# Arduino_MEGA_2560-Rev3.net
KiCad netlist of a schematic drawn in EAGLE
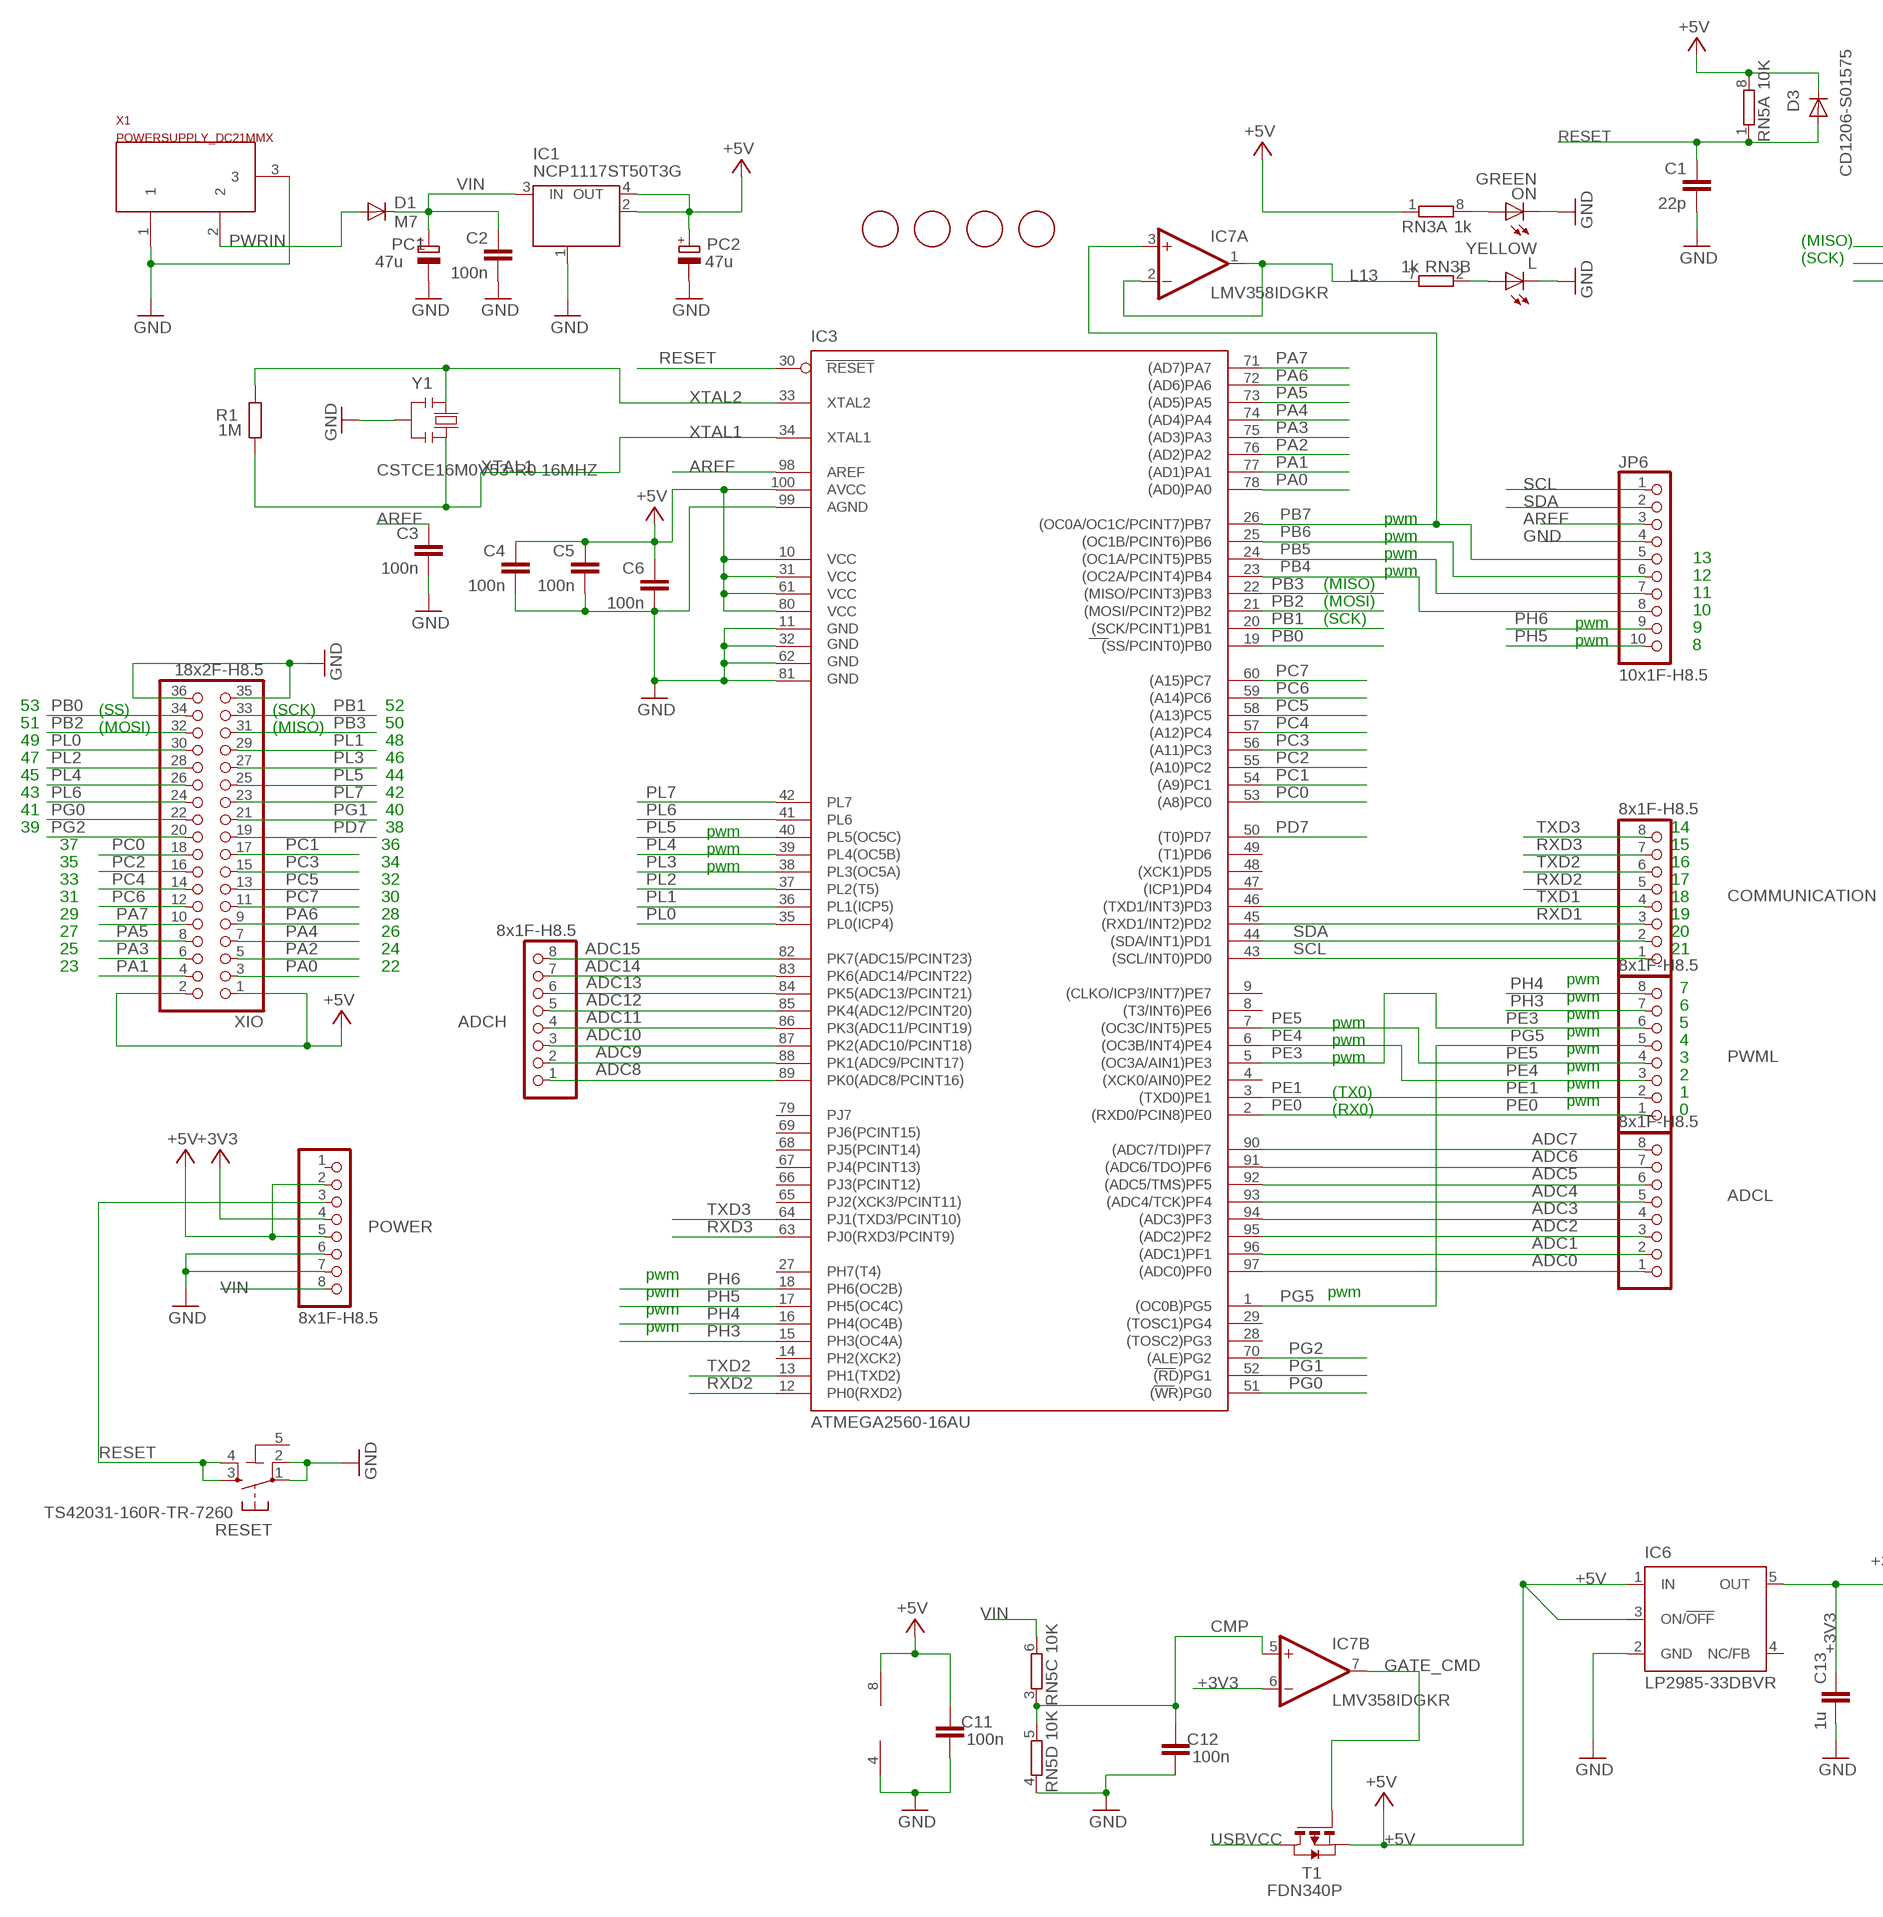
[diagram p0: schematic, sheet 1, part 1 of 2]
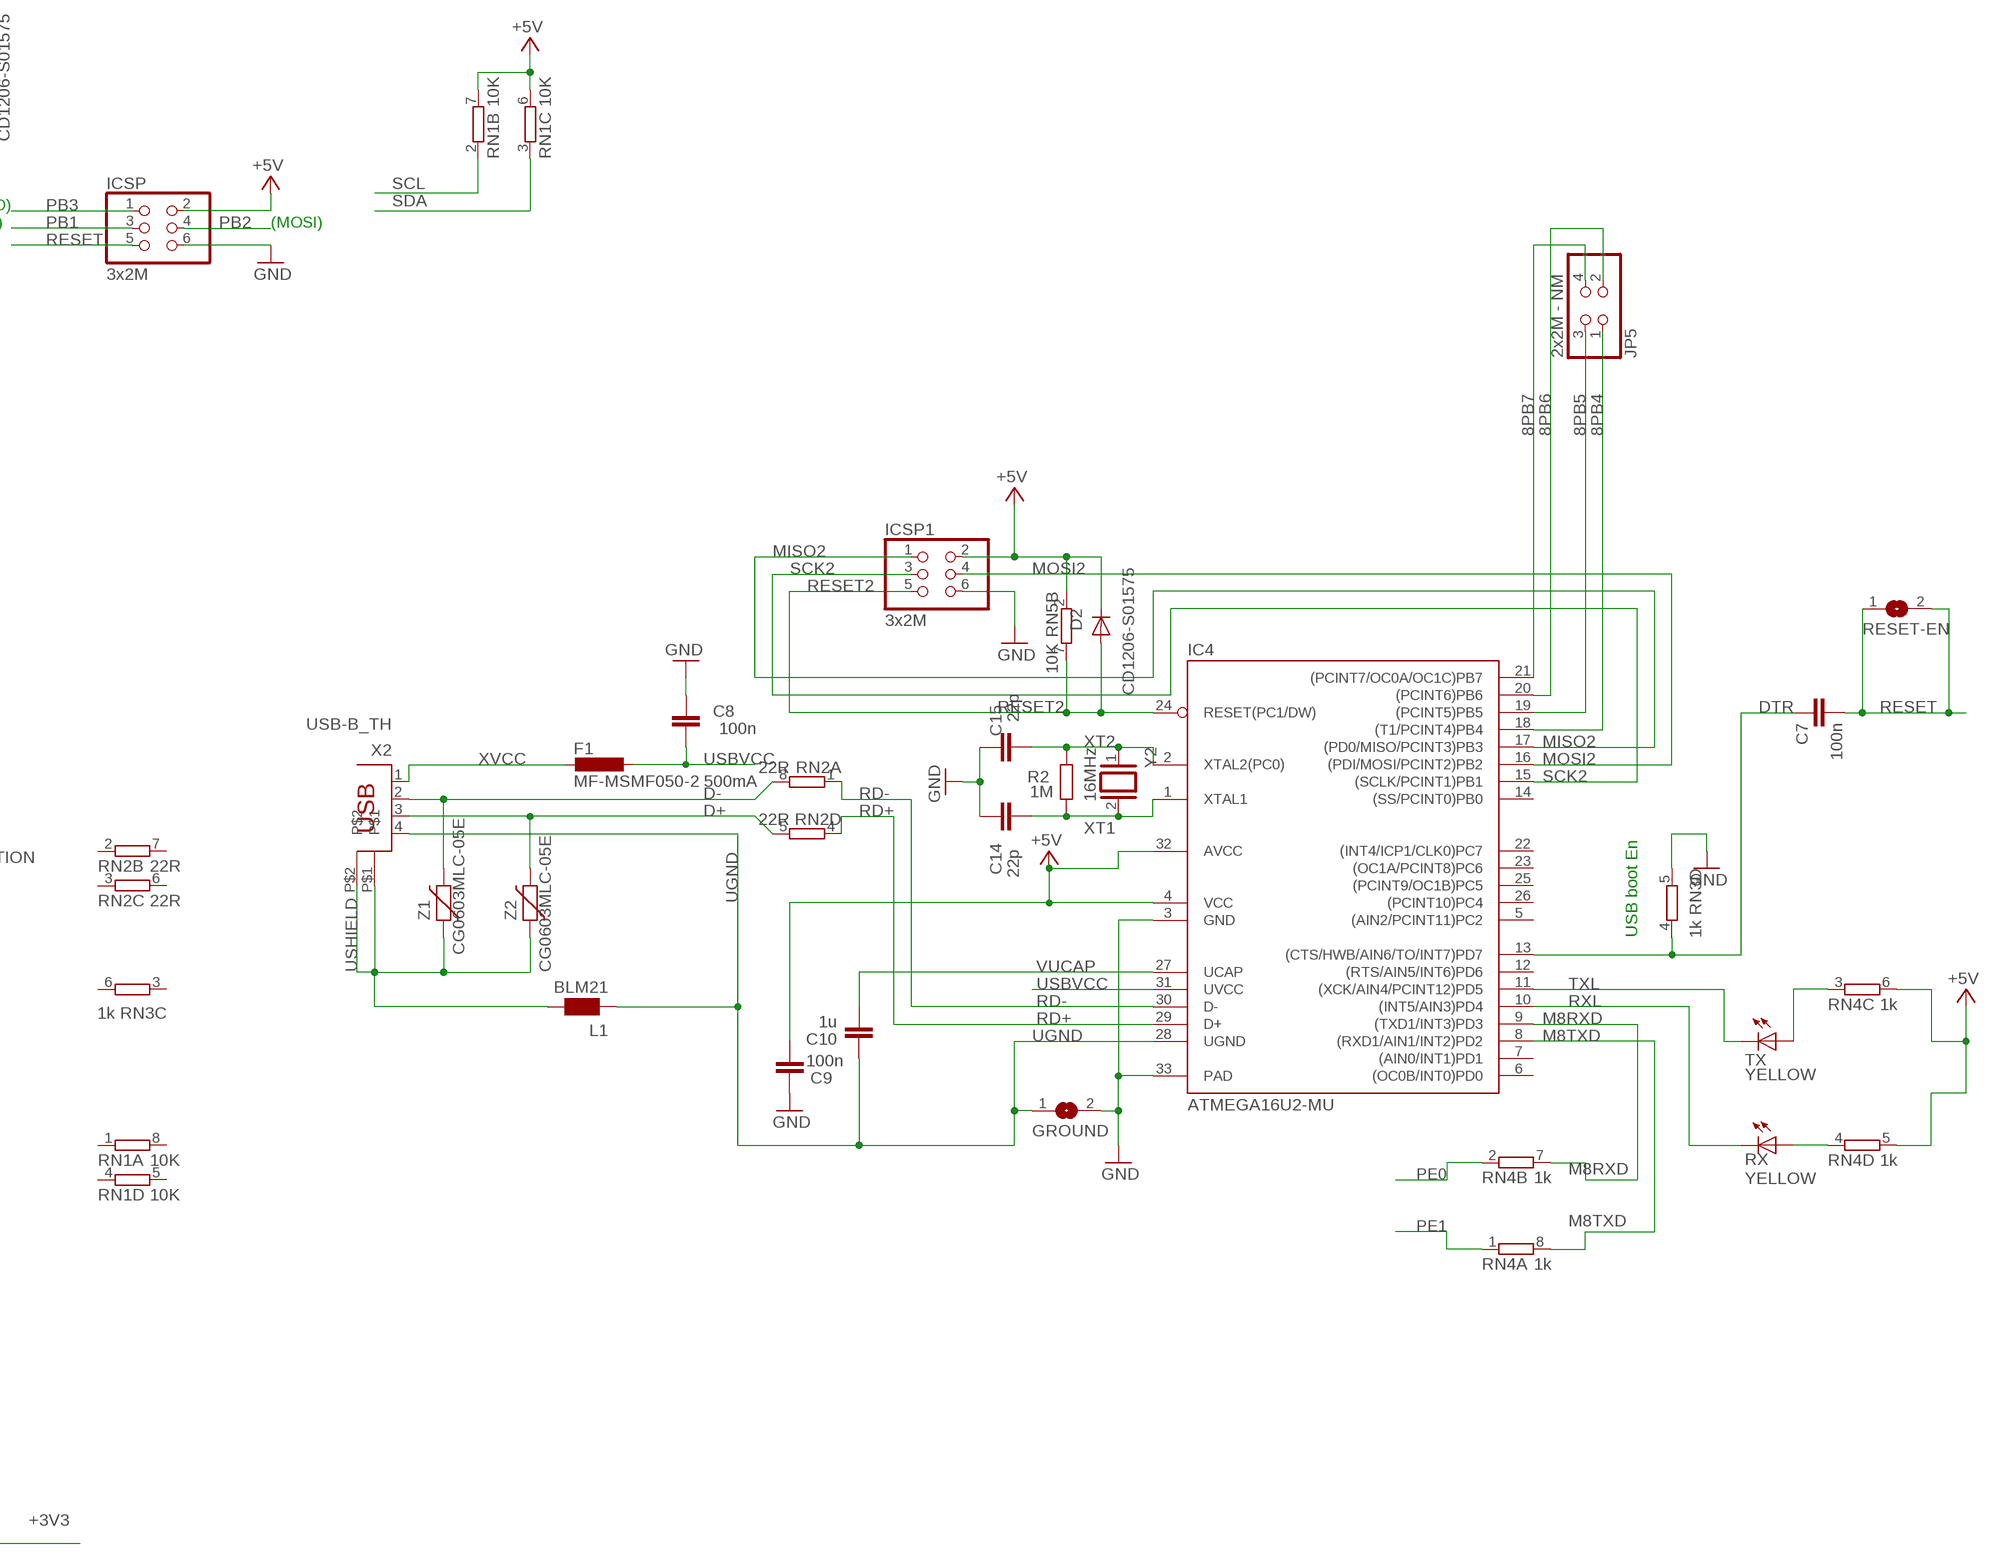
[diagram p1: schematic, sheet 1, part 2 of 2]

(export (version "E")
  (design (tool "Eeschema 10.0.6"))
  (components
    (comp (ref "ADCH")
      (value "8x1F-H8.5")
      (footprint "eagle-import:1X08")
      (libsource (lib "eagle-import") (part "PINHD-1X8"))
    )
    (comp (ref "ADCL")
      (value "8x1F-H8.5")
      (footprint "eagle-import:1X08")
      (libsource (lib "eagle-import") (part "PINHD-1X8"))
    )
    (comp (ref "C1")
      (value "22p")
      (footprint "eagle-import:C0603-ROUND")
      (libsource (lib "eagle-import") (part "C-EU0603-RND"))
    )
    (comp (ref "C2")
      (value "100n")
      (footprint "eagle-import:C0603-ROUND")
      (libsource (lib "eagle-import") (part "C-EU0603-RND"))
    )
    (comp (ref "C3")
      (value "100n")
      (footprint "eagle-import:C0603-ROUND")
      (libsource (lib "eagle-import") (part "C-EU0603-RND"))
    )
    (comp (ref "C4")
      (value "100n")
      (footprint "eagle-import:C0603-ROUND")
      (libsource (lib "eagle-import") (part "C-EU0603-RND"))
    )
    (comp (ref "C5")
      (value "100n")
      (footprint "eagle-import:C0603-ROUND")
      (libsource (lib "eagle-import") (part "C-EU0603-RND"))
    )
    (comp (ref "C6")
      (value "100n")
      (footprint "eagle-import:C0603-ROUND")
      (libsource (lib "eagle-import") (part "C-EU0603-RND"))
    )
    (comp (ref "C7")
      (value "100n")
      (footprint "eagle-import:C0603-ROUND")
      (libsource (lib "eagle-import") (part "C-EU0603-RND"))
    )
    (comp (ref "C8")
      (value "100n")
      (footprint "eagle-import:C0603-ROUND")
      (libsource (lib "eagle-import") (part "C-EU0603-RND"))
    )
    (comp (ref "C9")
      (value "100n")
      (footprint "eagle-import:C0603-ROUND")
      (libsource (lib "eagle-import") (part "C-EU0603-RND"))
    )
    (comp (ref "C10")
      (value "1u")
      (footprint "eagle-import:C0603-ROUND")
      (libsource (lib "eagle-import") (part "C-EU0603-RND"))
    )
    (comp (ref "C11")
      (value "100n")
      (footprint "eagle-import:C0603-ROUND")
      (libsource (lib "eagle-import") (part "C-EU0603-RND"))
    )
    (comp (ref "C12")
      (value "100n")
      (footprint "eagle-import:C0603-ROUND")
      (libsource (lib "eagle-import") (part "C-EU0603-RND"))
    )
    (comp (ref "C13")
      (value "1u")
      (footprint "eagle-import:C0603-ROUND")
      (libsource (lib "eagle-import") (part "C-EU0603-RND"))
    )
    (comp (ref "C14")
      (value "22p")
      (footprint "eagle-import:C0603-ROUND")
      (libsource (lib "eagle-import") (part "C-EU0603-RND"))
    )
    (comp (ref "C15")
      (value "22p")
      (footprint "eagle-import:C0603-ROUND")
      (libsource (lib "eagle-import") (part "C-EU0603-RND"))
    )
    (comp (ref "COMMUNICATION")
      (value "8x1F-H8.5")
      (footprint "eagle-import:1X08")
      (libsource (lib "eagle-import") (part "PINHD-1X8"))
    )
    (comp (ref "D1")
      (value "M7")
      (footprint "eagle-import:SMB")
      (libsource (lib "eagle-import") (part "DIODE-SMB"))
    )
    (comp (ref "D2")
      (value "CD1206-S01575")
      (footprint "eagle-import:MINIMELF")
      (libsource (lib "eagle-import") (part "DIODE-MINIMELF"))
    )
    (comp (ref "D3")
      (value "CD1206-S01575")
      (footprint "eagle-import:MINIMELF")
      (libsource (lib "eagle-import") (part "DIODE-MINIMELF"))
    )
    (comp (ref "F1")
      (value "MF-MSMF050-2 500mA")
      (footprint "eagle-import:L1812")
      (libsource (lib "eagle-import") (part "L-EUL1812"))
    )
    (comp (ref "FD1")
      (value "FIDUCIALMOUNT")
      (footprint "eagle-import:FIDUCIA-MOUNT")
      (libsource (lib "eagle-import") (part "FIDUCIALMOUNT"))
    )
    (comp (ref "FD2")
      (value "FIDUCIALMOUNT")
      (footprint "eagle-import:FIDUCIA-MOUNT")
      (libsource (lib "eagle-import") (part "FIDUCIALMOUNT"))
    )
    (comp (ref "FD3")
      (value "FIDUCIALMOUNT")
      (footprint "eagle-import:FIDUCIA-MOUNT")
      (libsource (lib "eagle-import") (part "FIDUCIALMOUNT"))
    )
    (comp (ref "FD4")
      (value "FIDUCIALMOUNT")
      (footprint "eagle-import:FIDUCIA-MOUNT")
      (libsource (lib "eagle-import") (part "FIDUCIALMOUNT"))
    )
    (comp (ref "GROUND")
      (value "SJ")
      (footprint "eagle-import:SJ")
      (libsource (lib "eagle-import") (part "SJ"))
    )
    (comp (ref "IC1")
      (value "NCP1117ST50T3G")
      (footprint "eagle-import:SOT223")
      (libsource (lib "eagle-import") (part "MC33269ST-3.3T3"))
    )
    (comp (ref "IC3")
      (value "ATMEGA2560-16AU")
      (footprint "eagle-import:TQFP100")
      (libsource (lib "eagle-import") (part "ATMEGA2560AU2560-16"))
    )
    (comp (ref "IC4")
      (value "ATMEGA16U2-MU")
      (footprint "eagle-import:MLF32")
      (libsource (lib "eagle-import") (part "ATMEGA16U2-MU"))
    )
    (comp (ref "IC6")
      (value "LP2985-33DBVR")
      (footprint "eagle-import:SOT23-DBV")
      (libsource (lib "eagle-import") (part "LP2985-XXDBVR33"))
    )
    (comp (ref "IC7")
      (value "LMV358IDGKR")
      (footprint "eagle-import:MSOP08")
      (libsource (lib "eagle-import") (part "LMV358?MMX"))
    )
    (comp (ref "ICSP")
      (value "3x2M")
      (footprint "eagle-import:2X03")
      (libsource (lib "eagle-import") (part "PINHD-2X3"))
    )
    (comp (ref "ICSP1")
      (value "3x2M")
      (footprint "eagle-import:2X03")
      (libsource (lib "eagle-import") (part "PINHD-2X3"))
    )
    (comp (ref "JP5")
      (value "2x2M - NM")
      (footprint "eagle-import:2X02")
      (libsource (lib "eagle-import") (part "PINHD-2X2"))
    )
    (comp (ref "JP6")
      (value "10x1F-H8.5")
      (footprint "eagle-import:1X10")
      (libsource (lib "eagle-import") (part "PINHD-1X10_ARD"))
    )
    (comp (ref "L")
      (value "YELLOW")
      (footprint "eagle-import:CHIP-LED0805")
      (libsource (lib "eagle-import") (part "LEDCHIP-LED0805"))
    )
    (comp (ref "L1")
      (value "BLM21")
      (footprint "eagle-import:0805")
      (libsource (lib "eagle-import") (part "WE-CBF_0805"))
    )
    (comp (ref "ON")
      (value "GREEN")
      (footprint "eagle-import:CHIP-LED0805")
      (libsource (lib "eagle-import") (part "LEDCHIP-LED0805"))
    )
    (comp (ref "PC1")
      (value "47u")
      (footprint "eagle-import:PANASONIC_D")
      (libsource (lib "eagle-import") (part "CPOL-EUD"))
    )
    (comp (ref "PC2")
      (value "47u")
      (footprint "eagle-import:PANASONIC_D")
      (libsource (lib "eagle-import") (part "CPOL-EUD"))
    )
    (comp (ref "POWER")
      (value "8x1F-H8.5")
      (footprint "eagle-import:1X08")
      (libsource (lib "eagle-import") (part "PINHD-1X8"))
    )
    (comp (ref "PWML")
      (value "8x1F-H8.5")
      (footprint "eagle-import:1X08")
      (libsource (lib "eagle-import") (part "PINHD-1X8"))
    )
    (comp (ref "R1")
      (value "1M")
      (footprint "eagle-import:R0603-ROUND")
      (libsource (lib "eagle-import") (part "R-EU_R0603"))
    )
    (comp (ref "R2")
      (value "1M")
      (footprint "eagle-import:R0603-ROUND")
      (libsource (lib "eagle-import") (part "R-EU_R0603"))
    )
    (comp (ref "RESET")
      (value "TS42031-160R-TR-7260")
      (footprint "eagle-import:TS42")
      (libsource (lib "eagle-import") (part "TS42"))
    )
    (comp (ref "RESET-EN")
      (value "SJ")
      (footprint "eagle-import:SJ")
      (libsource (lib "eagle-import") (part "SJ"))
    )
    (comp (ref "RN1")
      (value "10K")
      (footprint "eagle-import:CAT16")
      (libsource (lib "eagle-import") (part "4R-NCAT16"))
    )
    (comp (ref "RN2")
      (value "22R")
      (footprint "eagle-import:CAY16")
      (libsource (lib "eagle-import") (part "4R-NCAY16"))
    )
    (comp (ref "RN3")
      (value "1k")
      (footprint "eagle-import:CAY16")
      (libsource (lib "eagle-import") (part "4R-NCAY16"))
    )
    (comp (ref "RN4")
      (value "1k")
      (footprint "eagle-import:CAY16")
      (libsource (lib "eagle-import") (part "4R-NCAY16"))
    )
    (comp (ref "RN5")
      (value "10K")
      (footprint "eagle-import:CAT16")
      (libsource (lib "eagle-import") (part "4R-NCAT16"))
    )
    (comp (ref "RX")
      (value "YELLOW")
      (footprint "eagle-import:CHIP-LED0805")
      (libsource (lib "eagle-import") (part "LEDCHIP-LED0805"))
    )
    (comp (ref "T1")
      (value "FDN340P")
      (footprint "eagle-import:SOT-23")
      (libsource (lib "eagle-import") (part "PMOSSOT23"))
    )
    (comp (ref "TX")
      (value "YELLOW")
      (footprint "eagle-import:CHIP-LED0805")
      (libsource (lib "eagle-import") (part "LEDCHIP-LED0805"))
    )
    (comp (ref "X1")
      (value "POWERSUPPLY_DC21MMX")
      (footprint "eagle-import:POWERSUPPLY_DC-21MM")
      (libsource (lib "eagle-import") (part "POWERSUPPLY_DC21MMX"))
    )
    (comp (ref "X2")
      (value "USB-B_TH")
      (footprint "eagle-import:PN61729")
      (libsource (lib "eagle-import") (part "PN61729"))
    )
    (comp (ref "XIO")
      (value "18x2F-H8.5")
      (footprint "eagle-import:2X18")
      (libsource (lib "eagle-import") (part "PINHD-2X18"))
    )
    (comp (ref "Y1")
      (value "CSTCE16M0V53-R0 16MHZ")
      (footprint "eagle-import:RESONATOR")
      (libsource (lib "eagle-import") (part "RESONATORMU"))
    )
    (comp (ref "Y2")
      (value "16MHz")
      (footprint "eagle-import:QS")
      (libsource (lib "eagle-import") (part "XTAL/S"))
    )
    (comp (ref "Z1")
      (value "CG0603MLC-05E")
      (footprint "eagle-import:CT_CN0603")
      (libsource (lib "eagle-import") (part "VARISTORCN0603"))
    )
    (comp (ref "Z2")
      (value "CG0603MLC-05E")
      (footprint "eagle-import:CT_CN0603")
      (libsource (lib "eagle-import") (part "VARISTORCN0603"))
    )
  )
  (nets
    (net (code "1") (name "+3V3") (class "Default")
      (node (ref "C13") (pin "2") (pinfunction "2_2") (pintype "passive"))
      (node (ref "IC6") (pin "5") (pinfunction "OUT_5") (pintype "passive"))
      (node (ref "IC7") (pin "6") (pinfunction "-IN_6") (pintype "input"))
      (node (ref "POWER") (pin "4") (pinfunction "4_4") (pintype "passive"))
    )
    (net (code "2") (name "+5V") (class "Default")
      (node (ref "C11") (pin "2") (pinfunction "2_2") (pintype "passive"))
      (node (ref "C4") (pin "1") (pinfunction "1_1") (pintype "passive"))
      (node (ref "C5") (pin "1") (pinfunction "1_1") (pintype "passive"))
      (node (ref "C6") (pin "1") (pinfunction "1_1") (pintype "passive"))
      (node (ref "C9") (pin "1") (pinfunction "1_1") (pintype "passive"))
      (node (ref "D2") (pin "C") (pinfunction "C_C") (pintype "passive"))
      (node (ref "D3") (pin "C") (pinfunction "C_C") (pintype "passive"))
      (node (ref "IC1") (pin "2") (pinfunction "OUT_2") (pintype "passive"))
      (node (ref "IC1") (pin "4") (pinfunction "OUT_4") (pintype "passive"))
      (node (ref "IC3") (pin "10") (pinfunction "VCC_10") (pintype "power_in"))
      (node (ref "IC3") (pin "100") (pinfunction "AVCC_100") (pintype "power_in"))
      (node (ref "IC3") (pin "31") (pinfunction "VCC1_31") (pintype "power_in"))
      (node (ref "IC3") (pin "61") (pinfunction "VCC2_61") (pintype "power_in"))
      (node (ref "IC3") (pin "80") (pinfunction "VCC3_80") (pintype "power_in"))
      (node (ref "IC4") (pin "32") (pinfunction "AVCC_32") (pintype "power_in"))
      (node (ref "IC4") (pin "4") (pinfunction "VCC_4") (pintype "power_in"))
      (node (ref "IC6") (pin "1") (pinfunction "IN_1") (pintype "input"))
      (node (ref "IC6") (pin "3") (pinfunction "ON/~{OFF}_3") (pintype "input"))
      (node (ref "IC7") (pin "8") (pinfunction "V+_8") (pintype "power_in"))
      (node (ref "ICSP") (pin "2") (pinfunction "2_2") (pintype "passive"))
      (node (ref "ICSP1") (pin "2") (pinfunction "2_2") (pintype "passive"))
      (node (ref "PC2") (pin "+") (pinfunction "+_+") (pintype "passive"))
      (node (ref "POWER") (pin "2") (pinfunction "2_2") (pintype "passive"))
      (node (ref "POWER") (pin "5") (pinfunction "5_5") (pintype "passive"))
      (node (ref "RN1") (pin "6") (pinfunction "2_6") (pintype "passive"))
      (node (ref "RN1") (pin "7") (pinfunction "2_7") (pintype "passive"))
      (node (ref "RN3") (pin "1") (pinfunction "1_1") (pintype "passive"))
      (node (ref "RN4") (pin "5") (pinfunction "2_5") (pintype "passive"))
      (node (ref "RN4") (pin "6") (pinfunction "2_6") (pintype "passive"))
      (node (ref "RN5") (pin "2") (pinfunction "1_2") (pintype "passive"))
      (node (ref "RN5") (pin "8") (pinfunction "2_8") (pintype "passive"))
      (node (ref "T1") (pin "2") (pinfunction "S_2") (pintype "passive"))
      (node (ref "XIO") (pin "1") (pinfunction "1_1") (pintype "passive"))
      (node (ref "XIO") (pin "2") (pinfunction "2_2") (pintype "passive"))
    )
    (net (code "3") (name "/5-GND") (class "Default")
      (node (ref "RESET") (pin "5") (pinfunction "5-GND_5") (pintype "power_in"))
    )
    (net (code "4") (name "/8PB4") (class "Default")
      (node (ref "IC4") (pin "18") (pinfunction "(T1/PCINT4)PB4_18") (pintype "bidirectional"))
      (node (ref "JP5") (pin "1") (pinfunction "1_1") (pintype "passive"))
    )
    (net (code "5") (name "/8PB5") (class "Default")
      (node (ref "IC4") (pin "19") (pinfunction "(PCINT5)PB5_19") (pintype "bidirectional"))
      (node (ref "JP5") (pin "3") (pinfunction "3_3") (pintype "passive"))
    )
    (net (code "6") (name "/8PB6") (class "Default")
      (node (ref "IC4") (pin "20") (pinfunction "(PCINT6)PB6_20") (pintype "bidirectional"))
      (node (ref "JP5") (pin "2") (pinfunction "2_2") (pintype "passive"))
    )
    (net (code "7") (name "/8PB7") (class "Default")
      (node (ref "IC4") (pin "21") (pinfunction "(PCINT7/OC0A/OC1C)PB7_21") (pintype "bidirectional"))
      (node (ref "JP5") (pin "4") (pinfunction "4_4") (pintype "passive"))
    )
    (net (code "8") (name "/ADC0") (class "Default")
      (node (ref "ADCL") (pin "1") (pinfunction "1_1") (pintype "passive"))
      (node (ref "IC3") (pin "97") (pinfunction "(ADC0)PF0_97") (pintype "bidirectional"))
    )
    (net (code "9") (name "/ADC1") (class "Default")
      (node (ref "ADCL") (pin "2") (pinfunction "2_2") (pintype "passive"))
      (node (ref "IC3") (pin "96") (pinfunction "(ADC1)PF1_96") (pintype "bidirectional"))
    )
    (net (code "10") (name "/ADC2") (class "Default")
      (node (ref "ADCL") (pin "3") (pinfunction "3_3") (pintype "passive"))
      (node (ref "IC3") (pin "95") (pinfunction "(ADC2)PF2_95") (pintype "bidirectional"))
    )
    (net (code "11") (name "/ADC3") (class "Default")
      (node (ref "ADCL") (pin "4") (pinfunction "4_4") (pintype "passive"))
      (node (ref "IC3") (pin "94") (pinfunction "(ADC3)PF3_94") (pintype "bidirectional"))
    )
    (net (code "12") (name "/ADC4") (class "Default")
      (node (ref "ADCL") (pin "5") (pinfunction "5_5") (pintype "passive"))
      (node (ref "IC3") (pin "93") (pinfunction "(ADC4/TCK)PF4_93") (pintype "bidirectional"))
    )
    (net (code "13") (name "/ADC5") (class "Default")
      (node (ref "ADCL") (pin "6") (pinfunction "6_6") (pintype "passive"))
      (node (ref "IC3") (pin "92") (pinfunction "(ADC5/TMS)PF5_92") (pintype "bidirectional"))
    )
    (net (code "14") (name "/ADC6") (class "Default")
      (node (ref "ADCL") (pin "7") (pinfunction "7_7") (pintype "passive"))
      (node (ref "IC3") (pin "91") (pinfunction "(ADC6/TDO)PF6_91") (pintype "bidirectional"))
    )
    (net (code "15") (name "/ADC7") (class "Default")
      (node (ref "ADCL") (pin "8") (pinfunction "8_8") (pintype "passive"))
      (node (ref "IC3") (pin "90") (pinfunction "(ADC7/TDI)PF7_90") (pintype "bidirectional"))
    )
    (net (code "16") (name "/ADC8") (class "Default")
      (node (ref "ADCH") (pin "1") (pinfunction "1_1") (pintype "passive"))
      (node (ref "IC3") (pin "89") (pinfunction "PK0(ADC8/PCINT16)_89") (pintype "bidirectional"))
    )
    (net (code "17") (name "/ADC9") (class "Default")
      (node (ref "ADCH") (pin "2") (pinfunction "2_2") (pintype "passive"))
      (node (ref "IC3") (pin "88") (pinfunction "PK1(ADC9/PCINT17)_88") (pintype "bidirectional"))
    )
    (net (code "18") (name "/ADC10") (class "Default")
      (node (ref "ADCH") (pin "3") (pinfunction "3_3") (pintype "passive"))
      (node (ref "IC3") (pin "87") (pinfunction "PK2(ADC10/PCINT18)_87") (pintype "bidirectional"))
    )
    (net (code "19") (name "/ADC11") (class "Default")
      (node (ref "ADCH") (pin "4") (pinfunction "4_4") (pintype "passive"))
      (node (ref "IC3") (pin "86") (pinfunction "PK3(ADC11/PCINT19)_86") (pintype "bidirectional"))
    )
    (net (code "20") (name "/ADC12") (class "Default")
      (node (ref "ADCH") (pin "5") (pinfunction "5_5") (pintype "passive"))
      (node (ref "IC3") (pin "85") (pinfunction "PK4(ADC12/PCINT20)_85") (pintype "bidirectional"))
    )
    (net (code "21") (name "/ADC13") (class "Default")
      (node (ref "ADCH") (pin "6") (pinfunction "6_6") (pintype "passive"))
      (node (ref "IC3") (pin "84") (pinfunction "PK5(ADC13/PCINT21)_84") (pintype "bidirectional"))
    )
    (net (code "22") (name "/ADC14") (class "Default")
      (node (ref "ADCH") (pin "7") (pinfunction "7_7") (pintype "passive"))
      (node (ref "IC3") (pin "83") (pinfunction "PK6(ADC14/PCINT22)_83") (pintype "bidirectional"))
    )
    (net (code "23") (name "/ADC15") (class "Default")
      (node (ref "ADCH") (pin "8") (pinfunction "8_8") (pintype "passive"))
      (node (ref "IC3") (pin "82") (pinfunction "PK7(ADC15/PCINT23)_82") (pintype "bidirectional"))
    )
    (net (code "24") (name "/AREF") (class "Default")
      (node (ref "C3") (pin "1") (pinfunction "1_1") (pintype "passive"))
      (node (ref "IC3") (pin "98") (pinfunction "AREF_98") (pintype "bidirectional"))
      (node (ref "JP6") (pin "3") (pinfunction "3_3") (pintype "passive"))
    )
    (net (code "25") (name "/CMP") (class "Default")
      (node (ref "C12") (pin "2") (pinfunction "2_2") (pintype "passive"))
      (node (ref "IC7") (pin "5") (pinfunction "+IN_5") (pintype "input"))
      (node (ref "RN5") (pin "3") (pinfunction "1_3") (pintype "passive"))
      (node (ref "RN5") (pin "5") (pinfunction "2_5") (pintype "passive"))
    )
    (net (code "26") (name "/D+") (class "Default")
      (node (ref "RN2") (pin "5") (pinfunction "2_5") (pintype "passive"))
      (node (ref "X2") (pin "3") (pinfunction "3_3") (pintype "bidirectional"))
      (node (ref "Z2") (pin "2") (pinfunction "2_2") (pintype "passive"))
    )
    (net (code "27") (name "/D-") (class "Default")
      (node (ref "RN2") (pin "8") (pinfunction "2_8") (pintype "passive"))
      (node (ref "X2") (pin "2") (pinfunction "2_2") (pintype "bidirectional"))
      (node (ref "Z1") (pin "2") (pinfunction "2_2") (pintype "passive"))
    )
    (net (code "28") (name "/DTR") (class "Default")
      (node (ref "C7") (pin "1") (pinfunction "1_1") (pintype "passive"))
      (node (ref "IC4") (pin "13") (pinfunction "(CTS/HWB/AIN6/TO/INT7)PD7_13") (pintype "bidirectional"))
      (node (ref "RN3") (pin "4") (pinfunction "1_4") (pintype "passive"))
    )
    (net (code "29") (name "/GATE_CMD") (class "Default")
      (node (ref "IC7") (pin "7") (pinfunction "OUT_7") (pintype "output"))
      (node (ref "T1") (pin "3") (pinfunction "G_3") (pintype "passive"))
    )
    (net (code "30") (name "/L13") (class "Default")
      (node (ref "IC7") (pin "1") (pinfunction "OUT_1") (pintype "output"))
      (node (ref "IC7") (pin "2") (pinfunction "-IN_2") (pintype "input"))
      (node (ref "RN3") (pin "7") (pinfunction "2_7") (pintype "passive"))
    )
    (net (code "31") (name "/M8RXD") (class "Default")
      (node (ref "IC4") (pin "9") (pinfunction "(TXD1/INT3)PD3_9") (pintype "bidirectional"))
      (node (ref "RN4") (pin "7") (pinfunction "2_7") (pintype "passive"))
    )
    (net (code "32") (name "/M8TXD") (class "Default")
      (node (ref "IC4") (pin "8") (pinfunction "(RXD1/AIN1/INT2)PD2_8") (pintype "bidirectional"))
      (node (ref "RN4") (pin "8") (pinfunction "2_8") (pintype "passive"))
    )
    (net (code "33") (name "/MISO2") (class "Default")
      (node (ref "IC4") (pin "17") (pinfunction "(PD0/MISO/PCINT3)PB3_17") (pintype "bidirectional"))
      (node (ref "ICSP1") (pin "1") (pinfunction "1_1") (pintype "passive"))
    )
    (net (code "34") (name "/MOSI2") (class "Default")
      (node (ref "IC4") (pin "16") (pinfunction "(PDI/MOSI/PCINT2)PB2_16") (pintype "bidirectional"))
      (node (ref "ICSP1") (pin "4") (pinfunction "4_4") (pintype "passive"))
    )
    (net (code "35") (name "/PA0") (class "Default")
      (node (ref "IC3") (pin "78") (pinfunction "(AD0)PA0_78") (pintype "bidirectional"))
      (node (ref "XIO") (pin "3") (pinfunction "3_3") (pintype "passive"))
    )
    (net (code "36") (name "/PA1") (class "Default")
      (node (ref "IC3") (pin "77") (pinfunction "(AD1)PA1_77") (pintype "bidirectional"))
      (node (ref "XIO") (pin "4") (pinfunction "4_4") (pintype "passive"))
    )
    (net (code "37") (name "/PA2") (class "Default")
      (node (ref "IC3") (pin "76") (pinfunction "(AD2)PA2_76") (pintype "bidirectional"))
      (node (ref "XIO") (pin "5") (pinfunction "5_5") (pintype "passive"))
    )
    (net (code "38") (name "/PA3") (class "Default")
      (node (ref "IC3") (pin "75") (pinfunction "(AD3)PA3_75") (pintype "bidirectional"))
      (node (ref "XIO") (pin "6") (pinfunction "6_6") (pintype "passive"))
    )
    (net (code "39") (name "/PA4") (class "Default")
      (node (ref "IC3") (pin "74") (pinfunction "(AD4)PA4_74") (pintype "bidirectional"))
      (node (ref "XIO") (pin "7") (pinfunction "7_7") (pintype "passive"))
    )
    (net (code "40") (name "/PA5") (class "Default")
      (node (ref "IC3") (pin "73") (pinfunction "(AD5)PA5_73") (pintype "bidirectional"))
      (node (ref "XIO") (pin "8") (pinfunction "8_8") (pintype "passive"))
    )
    (net (code "41") (name "/PA6") (class "Default")
      (node (ref "IC3") (pin "72") (pinfunction "(AD6)PA6_72") (pintype "bidirectional"))
      (node (ref "XIO") (pin "9") (pinfunction "9_9") (pintype "passive"))
    )
    (net (code "42") (name "/PA7") (class "Default")
      (node (ref "IC3") (pin "71") (pinfunction "(AD7)PA7_71") (pintype "bidirectional"))
      (node (ref "XIO") (pin "10") (pinfunction "10_10") (pintype "passive"))
    )
    (net (code "43") (name "/PB0") (class "Default")
      (node (ref "IC3") (pin "19") (pinfunction "(SS/PCINT0)PB0_19") (pintype "bidirectional"))
      (node (ref "XIO") (pin "34") (pinfunction "34_34") (pintype "passive"))
    )
    (net (code "44") (name "/PB1") (class "Default")
      (node (ref "IC3") (pin "20") (pinfunction "(SCK/PCINT1)PB1_20") (pintype "bidirectional"))
      (node (ref "ICSP") (pin "3") (pinfunction "3_3") (pintype "passive"))
      (node (ref "XIO") (pin "33") (pinfunction "33_33") (pintype "passive"))
    )
    (net (code "45") (name "/PB2") (class "Default")
      (node (ref "IC3") (pin "21") (pinfunction "(MOSI/PCINT2)PB2_21") (pintype "bidirectional"))
      (node (ref "ICSP") (pin "4") (pinfunction "4_4") (pintype "passive"))
      (node (ref "XIO") (pin "32") (pinfunction "32_32") (pintype "passive"))
    )
    (net (code "46") (name "/PB3") (class "Default")
      (node (ref "IC3") (pin "22") (pinfunction "(MISO/PCINT3)PB3_22") (pintype "bidirectional"))
      (node (ref "ICSP") (pin "1") (pinfunction "1_1") (pintype "passive"))
      (node (ref "XIO") (pin "31") (pinfunction "31_31") (pintype "passive"))
    )
    (net (code "47") (name "/PB4") (class "Default")
      (node (ref "IC3") (pin "23") (pinfunction "(OC2A/PCINT4)PB4_23") (pintype "bidirectional"))
      (node (ref "JP6") (pin "8") (pinfunction "8_8") (pintype "passive"))
    )
    (net (code "48") (name "/PB5") (class "Default")
      (node (ref "IC3") (pin "24") (pinfunction "(OC1A/PCINT5)PB5_24") (pintype "bidirectional"))
      (node (ref "JP6") (pin "7") (pinfunction "7_7") (pintype "passive"))
    )
    (net (code "49") (name "/PB6") (class "Default")
      (node (ref "IC3") (pin "25") (pinfunction "(OC1B/PCINT6)PB6_25") (pintype "bidirectional"))
      (node (ref "JP6") (pin "6") (pinfunction "6_6") (pintype "passive"))
    )
    (net (code "50") (name "/PB7") (class "Default")
      (node (ref "IC3") (pin "26") (pinfunction "(OC0A/OC1C/PCINT7)PB7_26") (pintype "bidirectional"))
      (node (ref "IC7") (pin "3") (pinfunction "+IN_3") (pintype "input"))
      (node (ref "JP6") (pin "5") (pinfunction "5_5") (pintype "passive"))
    )
    (net (code "51") (name "/PC0") (class "Default")
      (node (ref "IC3") (pin "53") (pinfunction "(A8)PC0_53") (pintype "bidirectional"))
      (node (ref "XIO") (pin "18") (pinfunction "18_18") (pintype "passive"))
    )
    (net (code "52") (name "/PC1") (class "Default")
      (node (ref "IC3") (pin "54") (pinfunction "(A9)PC1_54") (pintype "bidirectional"))
      (node (ref "XIO") (pin "17") (pinfunction "17_17") (pintype "passive"))
    )
    (net (code "53") (name "/PC2") (class "Default")
      (node (ref "IC3") (pin "55") (pinfunction "(A10)PC2_55") (pintype "bidirectional"))
      (node (ref "XIO") (pin "16") (pinfunction "16_16") (pintype "passive"))
    )
    (net (code "54") (name "/PC3") (class "Default")
      (node (ref "IC3") (pin "56") (pinfunction "(A11)PC3_56") (pintype "bidirectional"))
      (node (ref "XIO") (pin "15") (pinfunction "15_15") (pintype "passive"))
    )
    (net (code "55") (name "/PC4") (class "Default")
      (node (ref "IC3") (pin "57") (pinfunction "(A12)PC4_57") (pintype "bidirectional"))
      (node (ref "XIO") (pin "14") (pinfunction "14_14") (pintype "passive"))
    )
    (net (code "56") (name "/PC5") (class "Default")
      (node (ref "IC3") (pin "58") (pinfunction "(A13)PC5_58") (pintype "bidirectional"))
      (node (ref "XIO") (pin "13") (pinfunction "13_13") (pintype "passive"))
    )
    (net (code "57") (name "/PC6") (class "Default")
      (node (ref "IC3") (pin "59") (pinfunction "(A14)PC6_59") (pintype "bidirectional"))
      (node (ref "XIO") (pin "12") (pinfunction "12_12") (pintype "passive"))
    )
    (net (code "58") (name "/PC7") (class "Default")
      (node (ref "IC3") (pin "60") (pinfunction "(A15)PC7_60") (pintype "bidirectional"))
      (node (ref "XIO") (pin "11") (pinfunction "11_11") (pintype "passive"))
    )
    (net (code "59") (name "/PD7") (class "Default")
      (node (ref "IC3") (pin "50") (pinfunction "(T0)PD7_50") (pintype "bidirectional"))
      (node (ref "XIO") (pin "19") (pinfunction "19_19") (pintype "passive"))
    )
    (net (code "60") (name "/PE0") (class "Default")
      (node (ref "IC3") (pin "2") (pinfunction "(RXD0/PCIN8)PE0_2") (pintype "bidirectional"))
      (node (ref "PWML") (pin "1") (pinfunction "1_1") (pintype "passive"))
      (node (ref "RN4") (pin "2") (pinfunction "1_2") (pintype "passive"))
    )
    (net (code "61") (name "/PE1") (class "Default")
      (node (ref "IC3") (pin "3") (pinfunction "(TXD0)PE1_3") (pintype "bidirectional"))
      (node (ref "PWML") (pin "2") (pinfunction "2_2") (pintype "passive"))
      (node (ref "RN4") (pin "1") (pinfunction "1_1") (pintype "passive"))
    )
    (net (code "62") (name "/PE3") (class "Default")
      (node (ref "IC3") (pin "5") (pinfunction "(OC3A/AIN1)PE3_5") (pintype "bidirectional"))
      (node (ref "PWML") (pin "6") (pinfunction "6_6") (pintype "passive"))
    )
    (net (code "63") (name "/PE4") (class "Default")
      (node (ref "IC3") (pin "6") (pinfunction "(OC3B/INT4)PE4_6") (pintype "bidirectional"))
      (node (ref "PWML") (pin "3") (pinfunction "3_3") (pintype "passive"))
    )
    (net (code "64") (name "/PE5") (class "Default")
      (node (ref "IC3") (pin "7") (pinfunction "(OC3C/INT5)PE5_7") (pintype "bidirectional"))
      (node (ref "PWML") (pin "4") (pinfunction "4_4") (pintype "passive"))
    )
    (net (code "65") (name "/PG0") (class "Default")
      (node (ref "IC3") (pin "51") (pinfunction "(WR)PG0_51") (pintype "bidirectional"))
      (node (ref "XIO") (pin "22") (pinfunction "22_22") (pintype "passive"))
    )
    (net (code "66") (name "/PG1") (class "Default")
      (node (ref "IC3") (pin "52") (pinfunction "(RD)PG1_52") (pintype "bidirectional"))
      (node (ref "XIO") (pin "21") (pinfunction "21_21") (pintype "passive"))
    )
    (net (code "67") (name "/PG2") (class "Default")
      (node (ref "IC3") (pin "70") (pinfunction "(ALE)PG2_70") (pintype "bidirectional"))
      (node (ref "XIO") (pin "20") (pinfunction "20_20") (pintype "passive"))
    )
    (net (code "68") (name "/PG5") (class "Default")
      (node (ref "IC3") (pin "1") (pinfunction "(OC0B)PG5_1") (pintype "bidirectional"))
      (node (ref "PWML") (pin "5") (pinfunction "5_5") (pintype "passive"))
    )
    (net (code "69") (name "/PH3") (class "Default")
      (node (ref "IC3") (pin "15") (pinfunction "PH3(OC4A)_15") (pintype "bidirectional"))
      (node (ref "PWML") (pin "7") (pinfunction "7_7") (pintype "passive"))
    )
    (net (code "70") (name "/PH4") (class "Default")
      (node (ref "IC3") (pin "16") (pinfunction "PH4(OC4B)_16") (pintype "bidirectional"))
      (node (ref "PWML") (pin "8") (pinfunction "8_8") (pintype "passive"))
    )
    (net (code "71") (name "/PH5") (class "Default")
      (node (ref "IC3") (pin "17") (pinfunction "PH5(OC4C)_17") (pintype "bidirectional"))
      (node (ref "JP6") (pin "10") (pinfunction "10_10") (pintype "passive"))
    )
    (net (code "72") (name "/PH6") (class "Default")
      (node (ref "IC3") (pin "18") (pinfunction "PH6(OC2B)_18") (pintype "bidirectional"))
      (node (ref "JP6") (pin "9") (pinfunction "9_9") (pintype "passive"))
    )
    (net (code "73") (name "/PL0") (class "Default")
      (node (ref "IC3") (pin "35") (pinfunction "PL0(ICP4)_35") (pintype "bidirectional"))
      (node (ref "XIO") (pin "30") (pinfunction "30_30") (pintype "passive"))
    )
    (net (code "74") (name "/PL1") (class "Default")
      (node (ref "IC3") (pin "36") (pinfunction "PL1(ICP5)_36") (pintype "bidirectional"))
      (node (ref "XIO") (pin "29") (pinfunction "29_29") (pintype "passive"))
    )
    (net (code "75") (name "/PL2") (class "Default")
      (node (ref "IC3") (pin "37") (pinfunction "PL2(T5)_37") (pintype "bidirectional"))
      (node (ref "XIO") (pin "28") (pinfunction "28_28") (pintype "passive"))
    )
    (net (code "76") (name "/PL3") (class "Default")
      (node (ref "IC3") (pin "38") (pinfunction "PL3(OC5A)_38") (pintype "bidirectional"))
      (node (ref "XIO") (pin "27") (pinfunction "27_27") (pintype "passive"))
    )
    (net (code "77") (name "/PL4") (class "Default")
      (node (ref "IC3") (pin "39") (pinfunction "PL4(OC5B)_39") (pintype "bidirectional"))
      (node (ref "XIO") (pin "26") (pinfunction "26_26") (pintype "passive"))
    )
    (net (code "78") (name "/PL5") (class "Default")
      (node (ref "IC3") (pin "40") (pinfunction "PL5(OC5C)_40") (pintype "bidirectional"))
      (node (ref "XIO") (pin "25") (pinfunction "25_25") (pintype "passive"))
    )
    (net (code "79") (name "/PL6") (class "Default")
      (node (ref "IC3") (pin "41") (pinfunction "PL6_41") (pintype "bidirectional"))
      (node (ref "XIO") (pin "24") (pinfunction "24_24") (pintype "passive"))
    )
    (net (code "80") (name "/PL7") (class "Default")
      (node (ref "IC3") (pin "42") (pinfunction "PL7_42") (pintype "bidirectional"))
      (node (ref "XIO") (pin "23") (pinfunction "23_23") (pintype "passive"))
    )
    (net (code "81") (name "/PWRIN") (class "Default")
      (node (ref "D1") (pin "A") (pinfunction "A_A") (pintype "passive"))
      (node (ref "X1") (pin "2") (pinfunction "2_2") (pintype "power_in"))
    )
    (net (code "82") (name "/RD+") (class "Default")
      (node (ref "IC4") (pin "29") (pinfunction "D+_29") (pintype "bidirectional"))
      (node (ref "RN2") (pin "4") (pinfunction "1_4") (pintype "passive"))
    )
    (net (code "83") (name "/RD-") (class "Default")
      (node (ref "IC4") (pin "30") (pinfunction "D-_30") (pintype "bidirectional"))
      (node (ref "RN2") (pin "1") (pinfunction "1_1") (pintype "passive"))
    )
    (net (code "84") (name "/RESET") (class "Default")
      (node (ref "C1") (pin "1") (pinfunction "1_1") (pintype "passive"))
      (node (ref "C7") (pin "2") (pinfunction "2_2") (pintype "passive"))
      (node (ref "D3") (pin "A") (pinfunction "A_A") (pintype "passive"))
      (node (ref "IC3") (pin "30") (pinfunction "RESET_30") (pintype "input"))
      (node (ref "ICSP") (pin "5") (pinfunction "5_5") (pintype "passive"))
      (node (ref "POWER") (pin "3") (pinfunction "3_3") (pintype "passive"))
      (node (ref "RESET") (pin "3") (pinfunction "3_3") (pintype "passive"))
      (node (ref "RESET") (pin "4") (pinfunction "4_4") (pintype "passive"))
      (node (ref "RESET-EN") (pin "1") (pinfunction "1_1") (pintype "passive"))
      (node (ref "RESET-EN") (pin "2") (pinfunction "2_2") (pintype "passive"))
      (node (ref "RN5") (pin "1") (pinfunction "1_1") (pintype "passive"))
    )
    (net (code "85") (name "/RESET2") (class "Default")
      (node (ref "D2") (pin "A") (pinfunction "A_A") (pintype "passive"))
      (node (ref "IC4") (pin "24") (pinfunction "RESET(PC1/DW)_24") (pintype "input"))
      (node (ref "ICSP1") (pin "5") (pinfunction "5_5") (pintype "passive"))
      (node (ref "RN5") (pin "7") (pinfunction "2_7") (pintype "passive"))
    )
    (net (code "86") (name "/RXD1") (class "Default")
      (node (ref "COMMUNICATION") (pin "3") (pinfunction "3_3") (pintype "passive"))
      (node (ref "IC3") (pin "45") (pinfunction "(RXD1/INT2)PD2_45") (pintype "bidirectional"))
    )
    (net (code "87") (name "/RXD2") (class "Default")
      (node (ref "COMMUNICATION") (pin "5") (pinfunction "5_5") (pintype "passive"))
      (node (ref "IC3") (pin "12") (pinfunction "PH0(RXD2)_12") (pintype "bidirectional"))
    )
    (net (code "88") (name "/RXD3") (class "Default")
      (node (ref "COMMUNICATION") (pin "7") (pinfunction "7_7") (pintype "passive"))
      (node (ref "IC3") (pin "63") (pinfunction "PJ0(RXD3/PCINT9)_63") (pintype "bidirectional"))
    )
    (net (code "89") (name "/RXL") (class "Default")
      (node (ref "IC4") (pin "10") (pinfunction "(INT5/AIN3)PD4_10") (pintype "bidirectional"))
      (node (ref "RX") (pin "C") (pinfunction "C_C") (pintype "passive"))
    )
    (net (code "90") (name "/SCK2") (class "Default")
      (node (ref "IC4") (pin "15") (pinfunction "(SCLK/PCINT1)PB1_15") (pintype "bidirectional"))
      (node (ref "ICSP1") (pin "3") (pinfunction "3_3") (pintype "passive"))
    )
    (net (code "91") (name "/SCL") (class "Default")
      (node (ref "COMMUNICATION") (pin "1") (pinfunction "1_1") (pintype "passive"))
      (node (ref "IC3") (pin "43") (pinfunction "(SCL/INT0)PD0_43") (pintype "bidirectional"))
      (node (ref "JP6") (pin "1") (pinfunction "1_1") (pintype "passive"))
      (node (ref "RN1") (pin "2") (pinfunction "1_2") (pintype "passive"))
    )
    (net (code "92") (name "/SDA") (class "Default")
      (node (ref "COMMUNICATION") (pin "2") (pinfunction "2_2") (pintype "passive"))
      (node (ref "IC3") (pin "44") (pinfunction "(SDA/INT1)PD1_44") (pintype "bidirectional"))
      (node (ref "JP6") (pin "2") (pinfunction "2_2") (pintype "passive"))
      (node (ref "RN1") (pin "3") (pinfunction "1_3") (pintype "passive"))
    )
    (net (code "93") (name "/TXD1") (class "Default")
      (node (ref "COMMUNICATION") (pin "4") (pinfunction "4_4") (pintype "passive"))
      (node (ref "IC3") (pin "46") (pinfunction "(TXD1/INT3)PD3_46") (pintype "bidirectional"))
    )
    (net (code "94") (name "/TXD2") (class "Default")
      (node (ref "COMMUNICATION") (pin "6") (pinfunction "6_6") (pintype "passive"))
      (node (ref "IC3") (pin "13") (pinfunction "PH1(TXD2)_13") (pintype "bidirectional"))
    )
    (net (code "95") (name "/TXD3") (class "Default")
      (node (ref "COMMUNICATION") (pin "8") (pinfunction "8_8") (pintype "passive"))
      (node (ref "IC3") (pin "64") (pinfunction "PJ1(TXD3/PCINT10)_64") (pintype "bidirectional"))
    )
    (net (code "96") (name "/TXL") (class "Default")
      (node (ref "IC4") (pin "11") (pinfunction "(XCK/AIN4/PCINT12)PD5_11") (pintype "bidirectional"))
      (node (ref "TX") (pin "C") (pinfunction "C_C") (pintype "passive"))
    )
    (net (code "97") (name "/UGND") (class "Default")
      (node (ref "C10") (pin "2") (pinfunction "2_2") (pintype "passive"))
      (node (ref "GROUND") (pin "1") (pinfunction "1_1") (pintype "passive"))
      (node (ref "IC4") (pin "28") (pinfunction "UGND_28") (pintype "power_in"))
      (node (ref "L1") (pin "1") (pinfunction "1_1") (pintype "passive"))
      (node (ref "X2") (pin "4") (pinfunction "4_4") (pintype "bidirectional"))
    )
    (net (code "98") (name "/USBVCC") (class "Default")
      (node (ref "C8") (pin "1") (pinfunction "1_1") (pintype "passive"))
      (node (ref "F1") (pin "1") (pinfunction "1_1") (pintype "passive"))
      (node (ref "IC4") (pin "31") (pinfunction "UVCC_31") (pintype "power_in"))
      (node (ref "T1") (pin "1") (pinfunction "D_1") (pintype "passive"))
    )
    (net (code "99") (name "/USHIELD") (class "Default")
      (node (ref "L1") (pin "2") (pinfunction "2_2") (pintype "passive"))
      (node (ref "X2") (pin "P$1") (pinfunction "P$1_P$1") (pintype "bidirectional"))
      (node (ref "X2") (pin "P$2") (pinfunction "P$2_P$2") (pintype "bidirectional"))
      (node (ref "Z1") (pin "1") (pinfunction "1_1") (pintype "passive"))
      (node (ref "Z2") (pin "1") (pinfunction "1_1") (pintype "passive"))
    )
    (net (code "100") (name "/VIN") (class "Default")
      (node (ref "C2") (pin "1") (pinfunction "1_1") (pintype "passive"))
      (node (ref "D1") (pin "C") (pinfunction "C_C") (pintype "passive"))
      (node (ref "IC1") (pin "3") (pinfunction "IN_3") (pintype "input"))
      (node (ref "PC1") (pin "+") (pinfunction "+_+") (pintype "passive"))
      (node (ref "POWER") (pin "8") (pinfunction "8_8") (pintype "passive"))
      (node (ref "RN5") (pin "6") (pinfunction "2_6") (pintype "passive"))
    )
    (net (code "101") (name "/VUCAP") (class "Default")
      (node (ref "C10") (pin "1") (pinfunction "1_1") (pintype "passive"))
      (node (ref "IC4") (pin "27") (pinfunction "UCAP_27") (pintype "passive"))
    )
    (net (code "102") (name "/XT1") (class "Default")
      (node (ref "C14") (pin "1") (pinfunction "1_1") (pintype "passive"))
      (node (ref "IC4") (pin "1") (pinfunction "XTAL1_1") (pintype "bidirectional"))
      (node (ref "R2") (pin "1") (pinfunction "1_1") (pintype "passive"))
      (node (ref "Y2") (pin "2") (pinfunction "2_2") (pintype "passive"))
    )
    (net (code "103") (name "/XT2") (class "Default")
      (node (ref "C15") (pin "1") (pinfunction "1_1") (pintype "passive"))
      (node (ref "IC4") (pin "2") (pinfunction "XTAL2(PC0)_2") (pintype "bidirectional"))
      (node (ref "R2") (pin "2") (pinfunction "2_2") (pintype "passive"))
      (node (ref "Y2") (pin "1") (pinfunction "1_1") (pintype "passive"))
    )
    (net (code "104") (name "/XTAL1") (class "Default")
      (node (ref "IC3") (pin "34") (pinfunction "XTAL1_34") (pintype "input"))
      (node (ref "R1") (pin "1") (pinfunction "1_1") (pintype "passive"))
      (node (ref "Y1") (pin "3") (pinfunction "3_3") (pintype "passive"))
    )
    (net (code "105") (name "/XTAL2") (class "Default")
      (node (ref "IC3") (pin "33") (pinfunction "XTAL2_33") (pintype "output"))
      (node (ref "R1") (pin "2") (pinfunction "2_2") (pintype "passive"))
      (node (ref "Y1") (pin "1") (pinfunction "1_1") (pintype "passive"))
    )
    (net (code "106") (name "/XVCC") (class "Default")
      (node (ref "F1") (pin "2") (pinfunction "2_2") (pintype "passive"))
      (node (ref "X2") (pin "1") (pinfunction "1_1") (pintype "bidirectional"))
    )
    (net (code "107") (name "GND") (class "Default")
      (node (ref "C1") (pin "2") (pinfunction "2_2") (pintype "passive"))
      (node (ref "C11") (pin "1") (pinfunction "1_1") (pintype "passive"))
      (node (ref "C12") (pin "1") (pinfunction "1_1") (pintype "passive"))
      (node (ref "C13") (pin "1") (pinfunction "1_1") (pintype "passive"))
      (node (ref "C14") (pin "2") (pinfunction "2_2") (pintype "passive"))
      (node (ref "C15") (pin "2") (pinfunction "2_2") (pintype "passive"))
      (node (ref "C2") (pin "2") (pinfunction "2_2") (pintype "passive"))
      (node (ref "C3") (pin "2") (pinfunction "2_2") (pintype "passive"))
      (node (ref "C4") (pin "2") (pinfunction "2_2") (pintype "passive"))
      (node (ref "C5") (pin "2") (pinfunction "2_2") (pintype "passive"))
      (node (ref "C6") (pin "2") (pinfunction "2_2") (pintype "passive"))
      (node (ref "C8") (pin "2") (pinfunction "2_2") (pintype "passive"))
      (node (ref "C9") (pin "2") (pinfunction "2_2") (pintype "passive"))
      (node (ref "GROUND") (pin "2") (pinfunction "2_2") (pintype "passive"))
      (node (ref "IC1") (pin "1") (pinfunction "GND/ADJ_1") (pintype "input"))
      (node (ref "IC3") (pin "11") (pinfunction "GND_11") (pintype "power_in"))
      (node (ref "IC3") (pin "32") (pinfunction "GND1_32") (pintype "power_in"))
      (node (ref "IC3") (pin "62") (pinfunction "GND2_62") (pintype "power_in"))
      (node (ref "IC3") (pin "81") (pinfunction "GND3_81") (pintype "power_in"))
      (node (ref "IC3") (pin "99") (pinfunction "AGND_99") (pintype "power_in"))
      (node (ref "IC4") (pin "3") (pinfunction "GND_3") (pintype "power_in"))
      (node (ref "IC4") (pin "33") (pinfunction "PAD_33") (pintype "power_in"))
      (node (ref "IC6") (pin "2") (pinfunction "GND_2") (pintype "power_in"))
      (node (ref "IC7") (pin "4") (pinfunction "V-_4") (pintype "power_in"))
      (node (ref "ICSP") (pin "6") (pinfunction "6_6") (pintype "passive"))
      (node (ref "ICSP1") (pin "6") (pinfunction "6_6") (pintype "passive"))
      (node (ref "JP6") (pin "4") (pinfunction "4_4") (pintype "passive"))
      (node (ref "L") (pin "C") (pinfunction "C_C") (pintype "passive"))
      (node (ref "ON") (pin "C") (pinfunction "C_C") (pintype "passive"))
      (node (ref "PC1") (pin "-") (pinfunction "-_-") (pintype "passive"))
      (node (ref "PC2") (pin "-") (pinfunction "-_-") (pintype "passive"))
      (node (ref "POWER") (pin "6") (pinfunction "6_6") (pintype "passive"))
      (node (ref "POWER") (pin "7") (pinfunction "7_7") (pintype "passive"))
      (node (ref "RESET") (pin "1") (pinfunction "1_1") (pintype "passive"))
      (node (ref "RESET") (pin "2") (pinfunction "2_2") (pintype "passive"))
      (node (ref "RN3") (pin "5") (pinfunction "2_5") (pintype "passive"))
      (node (ref "RN5") (pin "4") (pinfunction "1_4") (pintype "passive"))
      (node (ref "X1") (pin "1") (pinfunction "1_1") (pintype "power_in"))
      (node (ref "X1") (pin "3") (pinfunction "3_3") (pintype "power_in"))
      (node (ref "XIO") (pin "35") (pinfunction "35_35") (pintype "passive"))
      (node (ref "XIO") (pin "36") (pinfunction "36_36") (pintype "passive"))
      (node (ref "Y1") (pin "2") (pinfunction "2_2") (pintype "passive"))
    )
    (net (code "108") (name "Net-(RN3A-2)") (class "Default")
      (node (ref "ON") (pin "A") (pinfunction "A_A") (pintype "passive"))
      (node (ref "RN3") (pin "8") (pinfunction "2_8") (pintype "passive"))
    )
    (net (code "109") (name "Net-(RN3B-1)") (class "Default")
      (node (ref "L") (pin "A") (pinfunction "A_A") (pintype "passive"))
      (node (ref "RN3") (pin "2") (pinfunction "1_2") (pintype "passive"))
    )
    (net (code "110") (name "Net-(RN4C-1)") (class "Default")
      (node (ref "RN4") (pin "3") (pinfunction "1_3") (pintype "passive"))
      (node (ref "TX") (pin "A") (pinfunction "A_A") (pintype "passive"))
    )
    (net (code "111") (name "Net-(RN4D-1)") (class "Default")
      (node (ref "RN4") (pin "4") (pinfunction "1_4") (pintype "passive"))
      (node (ref "RX") (pin "A") (pinfunction "A_A") (pintype "passive"))
    )
    (net (code "112") (name "unconnected-(IC3-(CLKO{slash}ICP3{slash}INT7)PE7-Pad9)") (class "Default")
      (node (ref "IC3") (pin "9") (pinfunction "(CLKO/ICP3/INT7)PE7_9") (pintype "bidirectional"))
    )
    (net (code "113") (name "unconnected-(IC3-(ICP1)PD4-Pad47)") (class "Default")
      (node (ref "IC3") (pin "47") (pinfunction "(ICP1)PD4_47") (pintype "bidirectional"))
    )
    (net (code "114") (name "unconnected-(IC3-(T1)PD6-Pad49)") (class "Default")
      (node (ref "IC3") (pin "49") (pinfunction "(T1)PD6_49") (pintype "bidirectional"))
    )
    (net (code "115") (name "unconnected-(IC3-(T3{slash}INT6)PE6-Pad8)") (class "Default")
      (node (ref "IC3") (pin "8") (pinfunction "(T3/INT6)PE6_8") (pintype "bidirectional"))
    )
    (net (code "116") (name "unconnected-(IC3-(TOSC1)PG4-Pad29)") (class "Default")
      (node (ref "IC3") (pin "29") (pinfunction "(TOSC1)PG4_29") (pintype "bidirectional"))
    )
    (net (code "117") (name "unconnected-(IC3-(TOSC2)PG3-Pad28)") (class "Default")
      (node (ref "IC3") (pin "28") (pinfunction "(TOSC2)PG3_28") (pintype "bidirectional"))
    )
    (net (code "118") (name "unconnected-(IC3-(XCK0{slash}AIN0)PE2-Pad4)") (class "Default")
      (node (ref "IC3") (pin "4") (pinfunction "(XCK0/AIN0)PE2_4") (pintype "bidirectional"))
    )
    (net (code "119") (name "unconnected-(IC3-(XCK1)PD5-Pad48)") (class "Default")
      (node (ref "IC3") (pin "48") (pinfunction "(XCK1)PD5_48") (pintype "bidirectional"))
    )
    (net (code "120") (name "unconnected-(IC3-PH2(XCK2)-Pad14)") (class "Default")
      (node (ref "IC3") (pin "14") (pinfunction "PH2(XCK2)_14") (pintype "bidirectional"))
    )
    (net (code "121") (name "unconnected-(IC3-PH7(T4)-Pad27)") (class "Default")
      (node (ref "IC3") (pin "27") (pinfunction "PH7(T4)_27") (pintype "bidirectional"))
    )
    (net (code "122") (name "unconnected-(IC3-PJ2(XCK3{slash}PCINT11)-Pad65)") (class "Default")
      (node (ref "IC3") (pin "65") (pinfunction "PJ2(XCK3/PCINT11)_65") (pintype "bidirectional"))
    )
    (net (code "123") (name "unconnected-(IC3-PJ3(PCINT12)-Pad66)") (class "Default")
      (node (ref "IC3") (pin "66") (pinfunction "PJ3(PCINT12)_66") (pintype "bidirectional"))
    )
    (net (code "124") (name "unconnected-(IC3-PJ4(PCINT13)-Pad67)") (class "Default")
      (node (ref "IC3") (pin "67") (pinfunction "PJ4(PCINT13)_67") (pintype "bidirectional"))
    )
    (net (code "125") (name "unconnected-(IC3-PJ5(PCINT14)-Pad68)") (class "Default")
      (node (ref "IC3") (pin "68") (pinfunction "PJ5(PCINT14)_68") (pintype "bidirectional"))
    )
    (net (code "126") (name "unconnected-(IC3-PJ6(PCINT15)-Pad69)") (class "Default")
      (node (ref "IC3") (pin "69") (pinfunction "PJ6(PCINT15)_69") (pintype "bidirectional"))
    )
    (net (code "127") (name "unconnected-(IC3-PJ7-Pad79)") (class "Default")
      (node (ref "IC3") (pin "79") (pinfunction "PJ7_79") (pintype "bidirectional"))
    )
    (net (code "128") (name "unconnected-(IC4-(AIN0{slash}INT1)PD1-Pad7)") (class "Default")
      (node (ref "IC4") (pin "7") (pinfunction "(AIN0/INT1)PD1_7") (pintype "bidirectional"))
    )
    (net (code "129") (name "unconnected-(IC4-(AIN2{slash}PCINT11)PC2-Pad5)") (class "Default")
      (node (ref "IC4") (pin "5") (pinfunction "(AIN2/PCINT11)PC2_5") (pintype "bidirectional"))
    )
    (net (code "130") (name "unconnected-(IC4-(INT4{slash}ICP1{slash}CLK0)PC7-Pad22)") (class "Default")
      (node (ref "IC4") (pin "22") (pinfunction "(INT4/ICP1/CLK0)PC7_22") (pintype "bidirectional"))
    )
    (net (code "131") (name "unconnected-(IC4-(OC0B{slash}INT0)PD0-Pad6)") (class "Default")
      (node (ref "IC4") (pin "6") (pinfunction "(OC0B/INT0)PD0_6") (pintype "bidirectional"))
    )
    (net (code "132") (name "unconnected-(IC4-(OC1A{slash}PCINT8)PC6-Pad23)") (class "Default")
      (node (ref "IC4") (pin "23") (pinfunction "(OC1A/PCINT8)PC6_23") (pintype "bidirectional"))
    )
    (net (code "133") (name "unconnected-(IC4-(PCINT9{slash}OC1B)PC5-Pad25)") (class "Default")
      (node (ref "IC4") (pin "25") (pinfunction "(PCINT9/OC1B)PC5_25") (pintype "bidirectional"))
    )
    (net (code "134") (name "unconnected-(IC4-(PCINT10)PC4-Pad26)") (class "Default")
      (node (ref "IC4") (pin "26") (pinfunction "(PCINT10)PC4_26") (pintype "bidirectional"))
    )
    (net (code "135") (name "unconnected-(IC4-(RTS{slash}AIN5{slash}INT6)PD6-Pad12)") (class "Default")
      (node (ref "IC4") (pin "12") (pinfunction "(RTS/AIN5/INT6)PD6_12") (pintype "bidirectional"))
    )
    (net (code "136") (name "unconnected-(IC4-(SS{slash}PCINT0)PB0-Pad14)") (class "Default")
      (node (ref "IC4") (pin "14") (pinfunction "(SS/PCINT0)PB0_14") (pintype "bidirectional"))
    )
    (net (code "137") (name "unconnected-(IC6-NC{slash}FB-Pad4)") (class "Default")
      (node (ref "IC6") (pin "4") (pinfunction "NC/FB_4") (pintype "passive"))
    )
    (net (code "138") (name "unconnected-(POWER-Pad1)") (class "Default")
      (node (ref "POWER") (pin "1") (pinfunction "1_1") (pintype "passive"))
    )
    (net (code "139") (name "unconnected-(RN1-Pad1)") (class "Default")
      (node (ref "RN1") (pin "1") (pinfunction "1_1") (pintype "passive"))
    )
    (net (code "140") (name "unconnected-(RN1A-2-Pad8)") (class "Default")
      (node (ref "RN1") (pin "8") (pinfunction "2_8") (pintype "passive"))
    )
    (net (code "141") (name "unconnected-(RN1D-1-Pad4)") (class "Default")
      (node (ref "RN1") (pin "4") (pinfunction "1_4") (pintype "passive"))
    )
    (net (code "142") (name "unconnected-(RN1D-2-Pad5)") (class "Default")
      (node (ref "RN1") (pin "5") (pinfunction "2_5") (pintype "passive"))
    )
    (net (code "143") (name "unconnected-(RN2B-1-Pad2)") (class "Default")
      (node (ref "RN2") (pin "2") (pinfunction "1_2") (pintype "passive"))
    )
    (net (code "144") (name "unconnected-(RN2B-2-Pad7)") (class "Default")
      (node (ref "RN2") (pin "7") (pinfunction "2_7") (pintype "passive"))
    )
    (net (code "145") (name "unconnected-(RN2C-1-Pad3)") (class "Default")
      (node (ref "RN2") (pin "3") (pinfunction "1_3") (pintype "passive"))
    )
    (net (code "146") (name "unconnected-(RN2C-2-Pad6)") (class "Default")
      (node (ref "RN2") (pin "6") (pinfunction "2_6") (pintype "passive"))
    )
    (net (code "147") (name "unconnected-(RN3C-1-Pad3)") (class "Default")
      (node (ref "RN3") (pin "3") (pinfunction "1_3") (pintype "passive"))
    )
    (net (code "148") (name "unconnected-(RN3C-2-Pad6)") (class "Default")
      (node (ref "RN3") (pin "6") (pinfunction "2_6") (pintype "passive"))
    )
  )
)
